# untitled.net
KiCad netlist of a schematic drawn in EAGLE
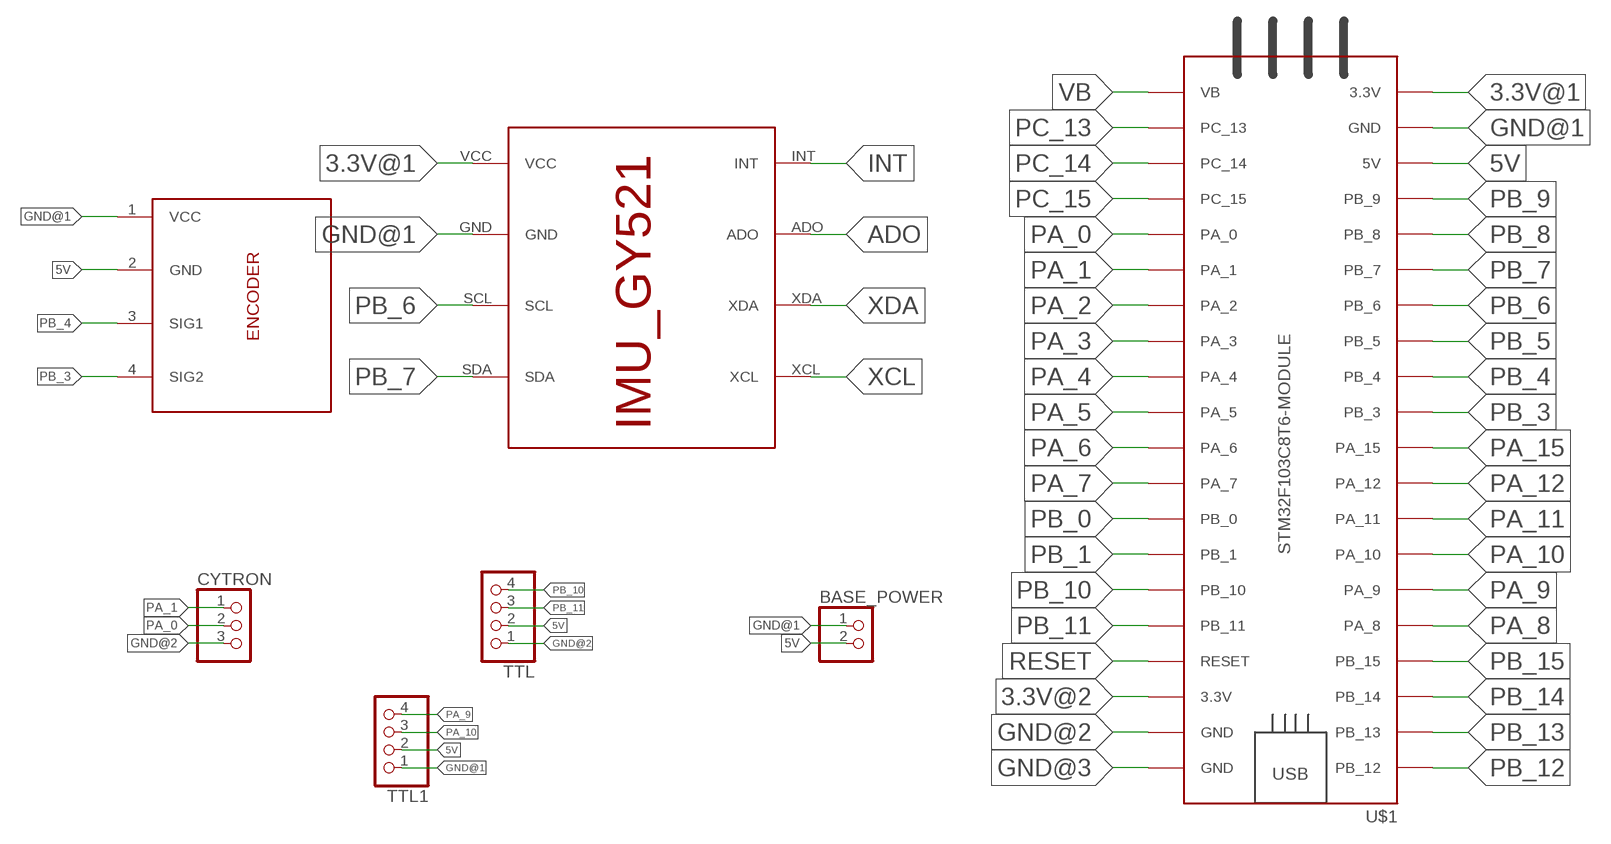
[diagram p0: schematic, sheet 1]

(export (version "E")
  (design (tool "Eeschema 10.0.6"))
  (components
    (comp (ref "BASE_POWER")
      (value "PINHD-2_DATA")
      (footprint "eagle-import:1X02_DATA")
      (libsource (lib "eagle-import") (part "PINHD-2_DATA"))
    )
    (comp (ref "CYTRON")
      (value "PINHD-3_DATA")
      (footprint "eagle-import:1X03_DATA")
      (libsource (lib "eagle-import") (part "PINHD-3_DATA"))
    )
    (comp (ref "TTL")
      (value "PINHD-4_DATA")
      (footprint "eagle-import:1X04_DATA")
      (libsource (lib "eagle-import") (part "PINHD-4_DATA"))
    )
    (comp (ref "TTL1")
      (value "PINHD-4_DATA")
      (footprint "eagle-import:1X04_DATA")
      (libsource (lib "eagle-import") (part "PINHD-4_DATA"))
    )
    (comp (ref "U$1")
      (value "STM32F103C8T6-MODULE")
      (footprint "eagle-import:STM32F103C8T6-MODULE")
      (libsource (lib "eagle-import") (part "STM32F103C8T6-MODULE"))
    )
    (comp (ref "U$2")
      (value "IMU_ROBOCON_GY521")
      (footprint "eagle-import:IMU_GY521")
      (libsource (lib "eagle-import") (part "IMU_ROBOCON_GY521"))
    )
    (comp (ref "U$3")
      (value "ENCODER")
      (footprint "eagle-import:1X04_DATA")
      (libsource (lib "eagle-import") (part "ENCODER"))
    )
  )
  (nets
    (net (code "1") (name "3.3V@1") (class "Default")
      (node (ref "U$1") (pin "3.3V_1") (pinfunction "3.3V_3.3V_1") (pintype "bidirectional"))
      (node (ref "U$2") (pin "VCC") (pinfunction "VCC_VCC") (pintype "bidirectional"))
    )
    (net (code "2") (name "3.3V@2") (class "Default")
      (node (ref "U$1") (pin "3.3V_2") (pinfunction "3.3V_3.3V_2") (pintype "bidirectional"))
    )
    (net (code "3") (name "5V") (class "Default")
      (node (ref "BASE_POWER") (pin "2") (pinfunction "2_2") (pintype "passive"))
      (node (ref "TTL") (pin "2") (pinfunction "2_2") (pintype "passive"))
      (node (ref "TTL1") (pin "2") (pinfunction "2_2") (pintype "passive"))
      (node (ref "U$1") (pin "5V") (pinfunction "5V_5V") (pintype "bidirectional"))
      (node (ref "U$3") (pin "2") (pinfunction "GND_2") (pintype "bidirectional"))
    )
    (net (code "4") (name "ADO") (class "Default")
      (node (ref "U$2") (pin "ADO") (pinfunction "ADO_ADO") (pintype "bidirectional"))
    )
    (net (code "5") (name "GND@1") (class "Default")
      (node (ref "BASE_POWER") (pin "1") (pinfunction "1_1") (pintype "passive"))
      (node (ref "TTL1") (pin "1") (pinfunction "1_1") (pintype "passive"))
      (node (ref "U$1") (pin "GND_1") (pinfunction "GND_GND_1") (pintype "bidirectional"))
      (node (ref "U$2") (pin "GND") (pinfunction "GND_GND") (pintype "bidirectional"))
      (node (ref "U$3") (pin "1") (pinfunction "VCC_1") (pintype "bidirectional"))
    )
    (net (code "6") (name "GND@2") (class "Default")
      (node (ref "CYTRON") (pin "3") (pinfunction "3_3") (pintype "passive"))
      (node (ref "TTL") (pin "1") (pinfunction "1_1") (pintype "passive"))
      (node (ref "U$1") (pin "GND_2") (pinfunction "GND_GND_2") (pintype "bidirectional"))
    )
    (net (code "7") (name "GND@3") (class "Default")
      (node (ref "U$1") (pin "GND_3") (pinfunction "GND_GND_3") (pintype "power_in"))
    )
    (net (code "8") (name "INT") (class "Default")
      (node (ref "U$2") (pin "INT") (pinfunction "INT_INT") (pintype "bidirectional"))
    )
    (net (code "9") (name "PA_0") (class "Default")
      (node (ref "CYTRON") (pin "2") (pinfunction "2_2") (pintype "passive"))
      (node (ref "U$1") (pin "PA_0") (pinfunction "PA_0_PA_0") (pintype "bidirectional"))
    )
    (net (code "10") (name "PA_1") (class "Default")
      (node (ref "CYTRON") (pin "1") (pinfunction "1_1") (pintype "passive"))
      (node (ref "U$1") (pin "PA_1") (pinfunction "PA_1_PA_1") (pintype "bidirectional"))
    )
    (net (code "11") (name "PA_2") (class "Default")
      (node (ref "U$1") (pin "PA_2") (pinfunction "PA_2_PA_2") (pintype "bidirectional"))
    )
    (net (code "12") (name "PA_3") (class "Default")
      (node (ref "U$1") (pin "PA_3") (pinfunction "PA_3_PA_3") (pintype "bidirectional"))
    )
    (net (code "13") (name "PA_4") (class "Default")
      (node (ref "U$1") (pin "PA_4") (pinfunction "PA_4_PA_4") (pintype "bidirectional"))
    )
    (net (code "14") (name "PA_5") (class "Default")
      (node (ref "U$1") (pin "PA_5") (pinfunction "PA_5_PA_5") (pintype "bidirectional"))
    )
    (net (code "15") (name "PA_6") (class "Default")
      (node (ref "U$1") (pin "PA_6") (pinfunction "PA_6_PA_6") (pintype "bidirectional"))
    )
    (net (code "16") (name "PA_7") (class "Default")
      (node (ref "U$1") (pin "PA_7") (pinfunction "PA_7_PA_7") (pintype "bidirectional"))
    )
    (net (code "17") (name "PA_8") (class "Default")
      (node (ref "U$1") (pin "PA_8") (pinfunction "PA_8_PA_8") (pintype "bidirectional"))
    )
    (net (code "18") (name "PA_9") (class "Default")
      (node (ref "TTL1") (pin "4") (pinfunction "4_4") (pintype "passive"))
      (node (ref "U$1") (pin "PA_9") (pinfunction "PA_9_PA_9") (pintype "bidirectional"))
    )
    (net (code "19") (name "PA_10") (class "Default")
      (node (ref "TTL1") (pin "3") (pinfunction "3_3") (pintype "passive"))
      (node (ref "U$1") (pin "PA_10") (pinfunction "PA_10_PA_10") (pintype "bidirectional"))
    )
    (net (code "20") (name "PA_11") (class "Default")
      (node (ref "U$1") (pin "PA_11") (pinfunction "PA_11_PA_11") (pintype "bidirectional"))
    )
    (net (code "21") (name "PA_12") (class "Default")
      (node (ref "U$1") (pin "PA_12") (pinfunction "PA_12_PA_12") (pintype "bidirectional"))
    )
    (net (code "22") (name "PA_15") (class "Default")
      (node (ref "U$1") (pin "PA_15") (pinfunction "PA_15_PA_15") (pintype "bidirectional"))
    )
    (net (code "23") (name "PB_0") (class "Default")
      (node (ref "U$1") (pin "PB_0") (pinfunction "PB_0_PB_0") (pintype "bidirectional"))
    )
    (net (code "24") (name "PB_1") (class "Default")
      (node (ref "U$1") (pin "PB_1") (pinfunction "PB_1_PB_1") (pintype "bidirectional"))
    )
    (net (code "25") (name "PB_3") (class "Default")
      (node (ref "U$1") (pin "PB_3") (pinfunction "PB_3_PB_3") (pintype "bidirectional"))
      (node (ref "U$3") (pin "4") (pinfunction "SIG2_4") (pintype "bidirectional"))
    )
    (net (code "26") (name "PB_4") (class "Default")
      (node (ref "U$1") (pin "PB_4") (pinfunction "PB_4_PB_4") (pintype "bidirectional"))
      (node (ref "U$3") (pin "3") (pinfunction "SIG1_3") (pintype "bidirectional"))
    )
    (net (code "27") (name "PB_5") (class "Default")
      (node (ref "U$1") (pin "PB_5") (pinfunction "PB_5_PB_5") (pintype "bidirectional"))
    )
    (net (code "28") (name "PB_6") (class "Default")
      (node (ref "U$1") (pin "PB_6") (pinfunction "PB_6_PB_6") (pintype "bidirectional"))
      (node (ref "U$2") (pin "SCL") (pinfunction "SCL_SCL") (pintype "bidirectional"))
    )
    (net (code "29") (name "PB_7") (class "Default")
      (node (ref "U$1") (pin "PB_7") (pinfunction "PB_7_PB_7") (pintype "bidirectional"))
      (node (ref "U$2") (pin "SDA") (pinfunction "SDA_SDA") (pintype "bidirectional"))
    )
    (net (code "30") (name "PB_8") (class "Default")
      (node (ref "U$1") (pin "PB_8") (pinfunction "PB_8_PB_8") (pintype "bidirectional"))
    )
    (net (code "31") (name "PB_9") (class "Default")
      (node (ref "U$1") (pin "PB_9") (pinfunction "PB_9_PB_9") (pintype "bidirectional"))
    )
    (net (code "32") (name "PB_10") (class "Default")
      (node (ref "TTL") (pin "4") (pinfunction "4_4") (pintype "passive"))
      (node (ref "U$1") (pin "PB_10") (pinfunction "PB_10_PB_10") (pintype "bidirectional"))
    )
    (net (code "33") (name "PB_11") (class "Default")
      (node (ref "TTL") (pin "3") (pinfunction "3_3") (pintype "passive"))
      (node (ref "U$1") (pin "PB_11") (pinfunction "PB_11_PB_11") (pintype "bidirectional"))
    )
    (net (code "34") (name "PB_12") (class "Default")
      (node (ref "U$1") (pin "PB_12") (pinfunction "PB_12_PB_12") (pintype "bidirectional"))
    )
    (net (code "35") (name "PB_13") (class "Default")
      (node (ref "U$1") (pin "PB_13") (pinfunction "PB_13_PB_13") (pintype "bidirectional"))
    )
    (net (code "36") (name "PB_14") (class "Default")
      (node (ref "U$1") (pin "PB_14") (pinfunction "PB_14_PB_14") (pintype "bidirectional"))
    )
    (net (code "37") (name "PB_15") (class "Default")
      (node (ref "U$1") (pin "PB_15") (pinfunction "PB_15_PB_15") (pintype "bidirectional"))
    )
    (net (code "38") (name "PC_13") (class "Default")
      (node (ref "U$1") (pin "PC_13") (pinfunction "PC_13_PC_13") (pintype "bidirectional"))
    )
    (net (code "39") (name "PC_14") (class "Default")
      (node (ref "U$1") (pin "PC_14") (pinfunction "PC_14_PC_14") (pintype "bidirectional"))
    )
    (net (code "40") (name "PC_15") (class "Default")
      (node (ref "U$1") (pin "PC_15") (pinfunction "PC_15_PC_15") (pintype "bidirectional"))
    )
    (net (code "41") (name "RESET") (class "Default")
      (node (ref "U$1") (pin "RESET") (pinfunction "RESET_RESET") (pintype "bidirectional"))
    )
    (net (code "42") (name "VB") (class "Default")
      (node (ref "U$1") (pin "VB") (pinfunction "VB_VB") (pintype "bidirectional"))
    )
    (net (code "43") (name "XCL") (class "Default")
      (node (ref "U$2") (pin "XCL") (pinfunction "XCL_XCL") (pintype "bidirectional"))
    )
    (net (code "44") (name "XDA") (class "Default")
      (node (ref "U$2") (pin "XDA") (pinfunction "XDA_XDA") (pintype "bidirectional"))
    )
  )
)
